# Schematic.net
KiCad netlist of a schematic drawn in Altium Designer
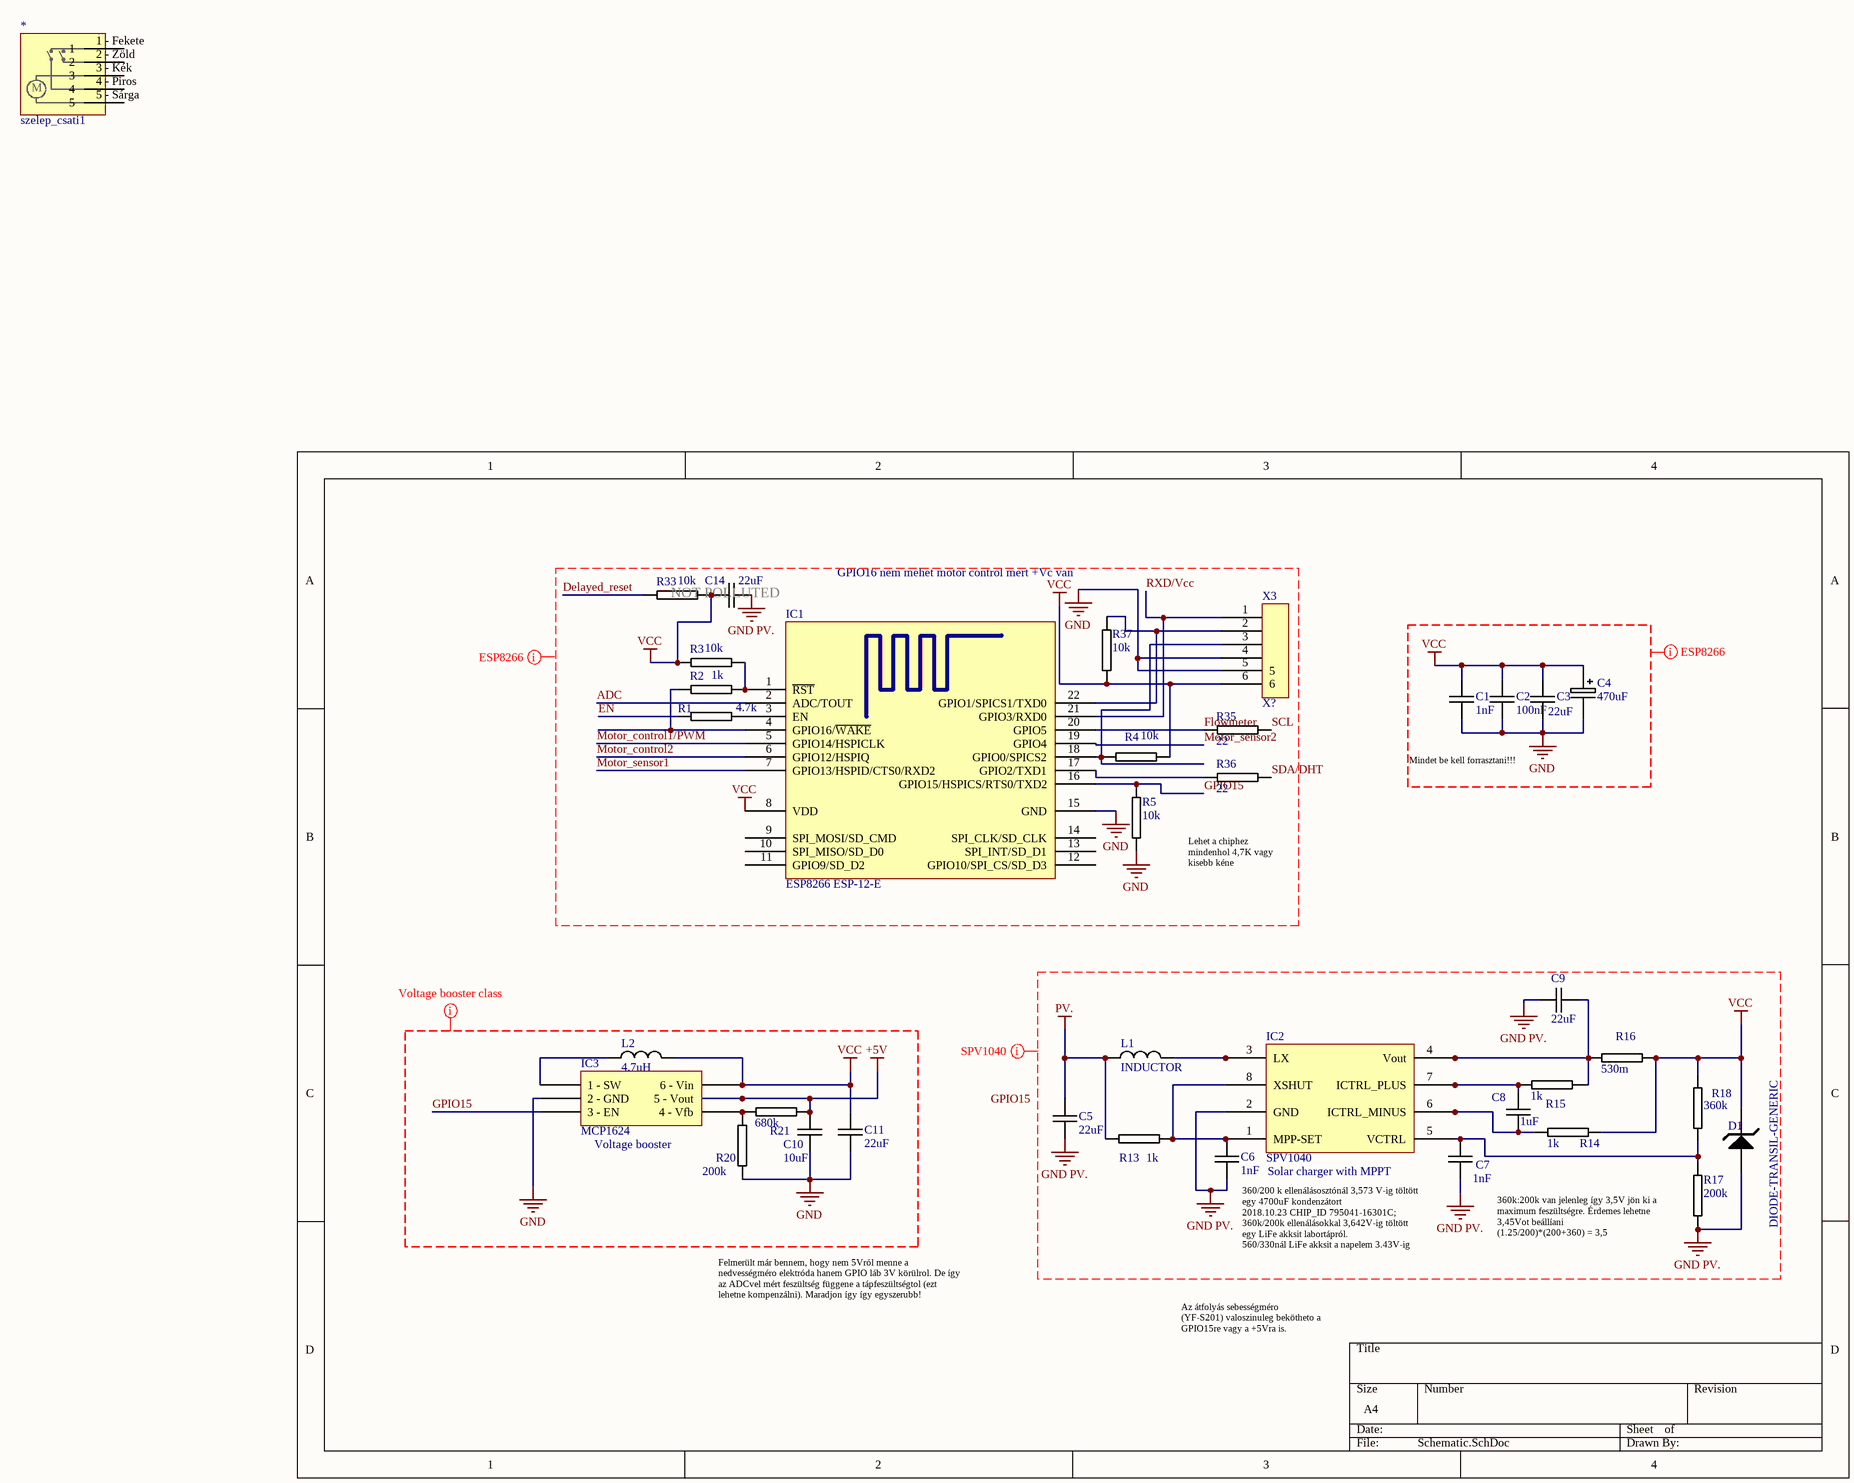
[diagram p0: Schematic.SchDoc]

(export (version "E")
  (design (tool "Eeschema 10.0.6"))
  (components
    (comp (ref "*")
      (value "szelep_csati1")
      (footprint "Szelep_csati")
      (libsource (lib "components") (part "szelep_csati1"))
    )
    (comp (ref "C1")
      (value "1nF")
      (footprint "0805C-TBD")
      (description "CAPACITOR 0805 CERAMIC")
      (libsource (lib "vh_altium_library") (part "0805C-100nF-25V-X7R-MUR"))
    )
    (comp (ref "C2")
      (value "100nF")
      (footprint "1206C-GENERIC")
      (description "GENERIC CAPACITOR NON POLARISED 1206")
      (fields
        (field (name "MANUFACTURER PART NUMBER") "GMK316F106ZL-T")
        (field (name "MANUFACTURER") "Taiyo Yuden")
      )
      (libsource (lib "vh_altium_library") (part "1206C-10U-35V-X7R"))
    )
    (comp (ref "C3")
      (value "22uF")
      (footprint "1206C-GENERIC")
      (description "GENERIC CAPACITOR NON POLARISED 1206")
      (fields
        (field (name "MANUFACTURER PART NUMBER") "GMK316F106ZL-T")
        (field (name "MANUFACTURER") "Taiyo Yuden")
      )
      (libsource (lib "vh_altium_library") (part "1206C-10U-35V-X7R"))
    )
    (comp (ref "C4")
      (value "470uF")
      (footprint "PANACAP-D-GENERIC")
      (description "GENERIC CAPACITOR POLARISED")
      (libsource (lib "vh_altium_library") (part "C+47U-6V3"))
    )
    (comp (ref "C5")
      (value "22uF")
      (footprint "1206C-GENERIC")
      (description "GENERIC CAPACITOR NON POLARISED 1206")
      (fields
        (field (name "MANUFACTURER PART NUMBER") "GMK316F106ZL-T")
        (field (name "MANUFACTURER") "Taiyo Yuden")
      )
      (libsource (lib "vh_altium_library") (part "1206C-10U-35V-X7R"))
    )
    (comp (ref "C6")
      (value "1nF")
      (footprint "CAPC200X125X100L40N")
      (description "CAPACITOR 0805 CERAMIC")
      (libsource (lib "vh_altium_library") (part "0805C-100nF-25V-X7R-MUR"))
    )
    (comp (ref "C7")
      (value "1nF")
      (footprint "CAPC200X125X100L40N")
      (description "CAPACITOR 0805 CERAMIC")
      (libsource (lib "components") (part "0805C-100nF-25V-X7R-MUR"))
    )
    (comp (ref "C8")
      (value "1uF")
      (footprint "CAPC200X125X100L40N")
      (description "CAPACITOR 0805 CERAMIC VALUE TO BE DETERMINED")
      (libsource (lib "SMD Capacitors 0805") (part "0805C-TBD"))
    )
    (comp (ref "C9")
      (value "22uF")
      (footprint "CAPC320X160X50L40N")
      (description "GENERIC CAPACITOR NON POLARISED 1206")
      (fields
        (field (name "MANUFACTURER PART NUMBER") "GMK316F106ZL-T")
        (field (name "MANUFACTURER") "Taiyo Yuden")
      )
      (libsource (lib "vh_altium_library") (part "1206C-10U-35V-X7R"))
    )
    (comp (ref "C10")
      (value "10uF")
      (footprint "1206C-GENERIC")
      (description "GENERIC CAPACITOR NON POLARISED 1206")
      (fields
        (field (name "MANUFACTURER PART NUMBER") "GMK316F106ZL-T")
        (field (name "MANUFACTURER") "Taiyo Yuden")
      )
      (libsource (lib "vh_altium_library") (part "1206C-10U-35V-X7R"))
    )
    (comp (ref "C11")
      (value "22uF")
      (footprint "1206C-GENERIC")
      (description "GENERIC CAPACITOR NON POLARISED 1206")
      (fields
        (field (name "MANUFACTURER PART NUMBER") "GMK316F106ZL-T")
        (field (name "MANUFACTURER") "Taiyo Yuden")
      )
      (libsource (lib "vh_altium_library") (part "1206C-10U-35V-X7R"))
    )
    (comp (ref "C14")
      (value "22uF")
      (footprint "0805C-GENERIC")
      (description "GENERIC CAPACITOR NON POLARISED0603")
      (libsource (lib "vh_altium_library") (part "C0805-GENERIC"))
    )
    (comp (ref "D1")
      (value "DIODE-TRANSIL-GENERIC")
      (footprint "SOD523")
      (description "GENERIC TRANSIL")
      (libsource (lib "vh_altium_library") (part "DIODE-TRANSIL-GENERIC"))
    )
    (comp (ref "IC1")
      (value "ESP8266 ESP-12-E")
      (footprint "ESP8266:ESP8266 ESP-12-E")
      (libsource (lib "ESP8266") (part "ESP8266 ESP-12-E"))
    )
    (comp (ref "IC2") (value "SPV1040") (footprint "SPV1040") (libsource (lib "components") (part "SPV1040")))
    (comp (ref "IC3") (value "MCP1624") (footprint "SOT23-6") (libsource (lib "MCP1623") (part "MCP1623")))
    (comp (ref "L1")
      (value "INDUCTOR")
      (footprint "INDM730X660X300L160X290N")
      (fields (field (name "LCSC PART #") "C132141"))
      (libsource (lib "vh_altium_library") (part "INDUCTOR"))
    )
    (comp (ref "L2")
      (value "4.7uH")
      (footprint "INDM2520X190N")
      (description "INDUCTOR")
      (fields (field (name "LCSC PART #") "C1049"))
      (libsource (lib "vh_altium_library") (part "INDUCTOR"))
    )
    (comp (ref "R1")
      (value "4.7k")
      (footprint "0805R-10K")
      (description "RESISTOR 0805 1/4 WATT THIN FILM")
      (libsource (lib "vh_altium_library") (part "0805R-10K"))
    )
    (comp (ref "R2")
      (value "1k")
      (footprint "1206FB-50Z")
      (description "0 vagy talan 1K? RESISTOR 0805 1/3 WATT")
      (libsource (lib "vh_altium_library") (part "0805R-1R"))
    )
    (comp (ref "R3")
      (value "10k")
      (footprint "0805R-10K")
      (description "RESISTOR 0805 1/4 WATT THIN FILM")
      (libsource (lib "vh_altium_library") (part "0805R-10K"))
    )
    (comp (ref "R4")
      (value "10k")
      (footprint "1206C-GENERIC")
      (description "RESISTOR 0805 1/4 WATT THIN FILM")
      (libsource (lib "vh_altium_library") (part "0805R-10K"))
    )
    (comp (ref "R5")
      (value "10k")
      (footprint "0805R-10K")
      (description "RESISTOR 0805 1/4 WATT THIN FILM")
      (libsource (lib "vh_altium_library") (part "0805R-10K"))
    )
    (comp (ref "R13")
      (value "1k")
      (footprint "RESC200X125X70L40N")
      (description "RESISTOR 0805 1/3 WATT")
      (libsource (lib "vh_altium_library") (part "0805R-1R"))
    )
    (comp (ref "R14")
      (value "1k")
      (footprint "RESC200X125X70L40N")
      (description "RESISTOR 0805 1/4 WATT THIN FILM")
      (libsource (lib "vh_altium_library") (part "0805R-1K"))
    )
    (comp (ref "R15")
      (value "1k")
      (footprint "RESC200X125X70L40N")
      (description "RESISTOR 0805 1/4 WATT THIN FILM")
      (libsource (lib "vh_altium_library") (part "0805R-1K"))
    )
    (comp (ref "R16")
      (value "530m")
      (footprint "RESC200X125X70L40N")
      (description "RESISTOR 0805 1/3 WATT")
      (libsource (lib "vh_altium_library") (part "0805R-1R"))
    )
    (comp (ref "R17")
      (value "200k")
      (footprint "RESC200X125X70L40N")
      (description "RESISTOR 0805 1/4 WATT THIN FILM")
      (libsource (lib "vh_altium_library") (part "0805R-680K"))
    )
    (comp (ref "R18")
      (value "360k")
      (footprint "RESC200X125X70L40N")
      (description "RESISTOR 0805 1/4 WATT THIN FILM")
      (libsource (lib "vh_altium_library") (part "0805R-680K"))
    )
    (comp (ref "R20")
      (value "200k")
      (footprint "RESC200X125X70L40N")
      (description "RESISTOR 0805 1/4 WATT THIN FILM")
      (libsource (lib "vh_altium_library") (part "0805R-820K"))
    )
    (comp (ref "R21")
      (value "680k")
      (footprint "RESC200X125X70L40N")
      (description "RESISTOR 0805 1/4 WATT THIN FILM")
      (libsource (lib "vh_altium_library") (part "0805R-560K"))
    )
    (comp (ref "R33")
      (value "10k")
      (footprint "0805R-10K")
      (description "RESISTOR 0805 1/4 WATT THIN FILM")
      (libsource (lib "vh_altium_library") (part "0805R-10K"))
    )
    (comp (ref "R35")
      (value "22")
      (footprint "0805R-22")
      (description "RESISTOR 0805 1/4 WATT THIN FILM")
      (libsource (lib "vh_altium_library") (part "0805R-22"))
    )
    (comp (ref "R36")
      (value "22")
      (footprint "0805R-22")
      (description "RESISTOR 0805 1/4 WATT THIN FILM")
      (libsource (lib "vh_altium_library") (part "0805R-22"))
    )
    (comp (ref "R37")
      (value "10k")
      (footprint "0805R-22")
      (description "RESISTOR 0805 1/4 WATT THIN FILM")
      (libsource (lib "vh_altium_library") (part "0805R-22"))
    )
    (comp (ref "X3")
      (value "X?")
      (footprint "program port")
      (libsource (lib "components") (part "program port"))
    )
  )
  (nets
    (net (code "1") (name "+5V") (class "Default")
      (node (ref "C10") (pin "1") (pintype "passive"))
      (node (ref "IC3") (pin "5") (pinfunction "5_-_Vout_5") (pintype "passive"))
      (node (ref "R21") (pin "2") (pintype "passive"))
    )
    (net (code "2") (name "/ADC") (class "Default")
      (node (ref "IC1") (pin "2") (pinfunction "ADC/TOUT_2") (pintype "passive"))
    )
    (net (code "3") (name "/Delayed_reset") (class "Default")
      (node (ref "R33") (pin "1") (pintype "passive"))
    )
    (net (code "4") (name "/EN") (class "Default") (node (ref "R1") (pin "1") (pintype "passive")))
    (net (code "5") (name "/Flowmeter") (class "Default")
      (node (ref "IC1") (pin "20") (pinfunction "GPIO5_20") (pintype "passive"))
      (node (ref "R35") (pin "2") (pintype "passive"))
    )
    (net (code "6") (name "/GPIO15") (class "Default")
      (node (ref "IC1") (pin "16") (pinfunction "GPIO15/HSPICS/RTS0/TXD2_16") (pintype "passive"))
      (node (ref "IC3") (pin "3") (pinfunction "3_-_EN_3") (pintype "passive"))
      (node (ref "R5") (pin "2") (pintype "passive"))
    )
    (net (code "7") (name "/Motor_control1{slash}PWM") (class "Default")
      (node (ref "IC1") (pin "5") (pinfunction "GPIO14/HSPICLK_5") (pintype "passive"))
    )
    (net (code "8") (name "/Motor_control2") (class "Default")
      (node (ref "IC1") (pin "6") (pinfunction "GPIO12/HSPIQ_6") (pintype "passive"))
    )
    (net (code "9") (name "/Motor_sensor1") (class "Default")
      (node (ref "IC1") (pin "7") (pinfunction "GPIO13/HSPID/CTS0/RXD2_7") (pintype "passive"))
    )
    (net (code "10") (name "/Motor_sensor2") (class "Default")
      (node (ref "IC1") (pin "19") (pinfunction "GPIO4_19") (pintype "passive"))
    )
    (net (code "11") (name "/RXD{slash}Vcc") (class "Default")
      (node (ref "IC1") (pin "21") (pinfunction "GPIO3/RXD0_21") (pintype "passive"))
      (node (ref "X3") (pin "1") (pinfunction "1_1") (pintype "passive"))
    )
    (net (code "12") (name "/SCL") (class "Default") (node (ref "R35") (pin "1") (pintype "passive")))
    (net (code "13") (name "/SDA{slash}DHT") (class "Default")
      (node (ref "R36") (pin "1") (pintype "passive"))
    )
    (net (code "14") (name "GND") (class "Default")
      (node (ref "C1") (pin "2") (pintype "passive"))
      (node (ref "C10") (pin "2") (pintype "passive"))
      (node (ref "C11") (pin "2") (pintype "passive"))
      (node (ref "C2") (pin "2") (pintype "passive"))
      (node (ref "C3") (pin "2") (pintype "passive"))
      (node (ref "C4") (pin "-") (pinfunction "-_-") (pintype "passive"))
      (node (ref "IC1") (pin "15") (pinfunction "GND_15") (pintype "passive"))
      (node (ref "IC3") (pin "2") (pinfunction "2_-_GND_2") (pintype "passive"))
      (node (ref "R20") (pin "2") (pintype "passive"))
      (node (ref "R5") (pin "1") (pintype "passive"))
      (node (ref "X3") (pin "4") (pinfunction "4_4") (pintype "passive"))
      (node (ref "X3") (pin "5") (pinfunction "5_5") (pintype "passive"))
    )
    (net (code "15") (name "GND PV.") (class "Default")
      (node (ref "C14") (pin "2") (pintype "passive"))
      (node (ref "C5") (pin "2") (pintype "passive"))
      (node (ref "C6") (pin "2") (pintype "passive"))
      (node (ref "C7") (pin "2") (pintype "passive"))
      (node (ref "C9") (pin "1") (pintype "passive"))
      (node (ref "D1") (pin "A") (pinfunction "A_A") (pintype "passive"))
      (node (ref "IC2") (pin "2") (pinfunction "GND_2") (pintype "passive"))
      (node (ref "R17") (pin "2") (pintype "passive"))
    )
    (net (code "16") (name "Net-(IC1-EN)") (class "Default")
      (node (ref "IC1") (pin "3") (pinfunction "EN_3") (pintype "passive"))
      (node (ref "R1") (pin "2") (pintype "passive"))
    )
    (net (code "17") (name "Net-(IC1-GPIO0{slash}SPICS2)") (class "Default")
      (node (ref "IC1") (pin "18") (pinfunction "GPIO0/SPICS2_18") (pintype "passive"))
      (node (ref "R4") (pin "1") (pintype "passive"))
      (node (ref "X3") (pin "3") (pinfunction "2_3") (pintype "passive"))
    )
    (net (code "18") (name "Net-(IC1-GPIO1{slash}SPICS1{slash}TXD0)") (class "Default")
      (node (ref "IC1") (pin "22") (pinfunction "GPIO1/SPICS1/TXD0_22") (pintype "passive"))
      (node (ref "R37") (pin "1") (pintype "passive"))
      (node (ref "X3") (pin "2") (pinfunction "2_2") (pintype "passive"))
    )
    (net (code "19") (name "Net-(IC1-GPIO2{slash}TXD1)") (class "Default")
      (node (ref "IC1") (pin "17") (pinfunction "GPIO2/TXD1_17") (pintype "passive"))
      (node (ref "R36") (pin "2") (pintype "passive"))
    )
    (net (code "20") (name "Net-(IC1-GPIO16{slash}~{WAKE})") (class "Default")
      (node (ref "IC1") (pin "4") (pinfunction "GPIO16/~{WAKE}_4") (pintype "passive"))
      (node (ref "R2") (pin "2") (pintype "passive"))
    )
    (net (code "21") (name "Net-(IC1-~{RST})") (class "Default")
      (node (ref "IC1") (pin "1") (pinfunction "~{RST}_1") (pintype "passive"))
      (node (ref "R2") (pin "1") (pintype "passive"))
      (node (ref "R3") (pin "2") (pintype "passive"))
    )
    (net (code "22") (name "Net-(IC2-ICTRL_MINUS)") (class "Default")
      (node (ref "C8") (pin "2") (pintype "passive"))
      (node (ref "IC2") (pin "6") (pinfunction "ICTRL_MINUS_6") (pintype "passive"))
      (node (ref "R14") (pin "2") (pintype "passive"))
    )
    (net (code "23") (name "Net-(IC2-ICTRL_PLUS)") (class "Default")
      (node (ref "C8") (pin "1") (pintype "passive"))
      (node (ref "IC2") (pin "7") (pinfunction "ICTRL_PLUS_7") (pintype "passive"))
      (node (ref "R15") (pin "2") (pintype "passive"))
    )
    (net (code "24") (name "Net-(IC2-LX)") (class "Default")
      (node (ref "IC2") (pin "3") (pinfunction "LX_3") (pintype "passive"))
      (node (ref "L1") (pin "2") (pinfunction "2_2") (pintype "passive"))
    )
    (net (code "25") (name "Net-(IC2-MPP-SET)") (class "Default")
      (node (ref "C6") (pin "1") (pintype "passive"))
      (node (ref "IC2") (pin "1") (pinfunction "MPP-SET_1") (pintype "passive"))
      (node (ref "IC2") (pin "8") (pinfunction "XSHUT_8") (pintype "passive"))
      (node (ref "R13") (pin "1") (pintype "passive"))
    )
    (net (code "26") (name "Net-(IC2-VCTRL)") (class "Default")
      (node (ref "C7") (pin "1") (pintype "passive"))
      (node (ref "IC2") (pin "5") (pinfunction "VCTRL_5") (pintype "passive"))
      (node (ref "R17") (pin "1") (pintype "passive"))
      (node (ref "R18") (pin "2") (pintype "passive"))
    )
    (net (code "27") (name "Net-(IC2-Vout)") (class "Default")
      (node (ref "C9") (pin "2") (pintype "passive"))
      (node (ref "IC2") (pin "4") (pinfunction "Vout_4") (pintype "passive"))
      (node (ref "R15") (pin "1") (pintype "passive"))
      (node (ref "R16") (pin "2") (pintype "passive"))
    )
    (net (code "28") (name "Net-(IC3-1_-_SW)") (class "Default")
      (node (ref "IC3") (pin "1") (pinfunction "1_-_SW_1") (pintype "passive"))
      (node (ref "L2") (pin "1") (pinfunction "1_1") (pintype "passive"))
    )
    (net (code "29") (name "Net-(IC3-4_-_Vfb)") (class "Default")
      (node (ref "IC3") (pin "4") (pinfunction "4_-_Vfb_4") (pintype "passive"))
      (node (ref "R20") (pin "1") (pintype "passive"))
      (node (ref "R21") (pin "1") (pintype "passive"))
    )
    (net (code "30") (name "PV.") (class "Default")
      (node (ref "C5") (pin "1") (pintype "passive"))
      (node (ref "L1") (pin "1") (pinfunction "1_1") (pintype "passive"))
      (node (ref "R13") (pin "2") (pintype "passive"))
    )
    (net (code "31") (name "VCC") (class "Default")
      (node (ref "C1") (pin "1") (pintype "passive"))
      (node (ref "C11") (pin "1") (pintype "passive"))
      (node (ref "C14") (pin "1") (pintype "passive"))
      (node (ref "C2") (pin "1") (pintype "passive"))
      (node (ref "C3") (pin "1") (pintype "passive"))
      (node (ref "C4") (pin "+") (pinfunction "+_+") (pintype "passive"))
      (node (ref "D1") (pin "K") (pinfunction "K_K") (pintype "passive"))
      (node (ref "IC1") (pin "8") (pinfunction "VDD_8") (pintype "passive"))
      (node (ref "IC3") (pin "6") (pinfunction "6_-_Vin_6") (pintype "passive"))
      (node (ref "L2") (pin "2") (pinfunction "2_2") (pintype "passive"))
      (node (ref "R14") (pin "1") (pintype "passive"))
      (node (ref "R16") (pin "1") (pintype "passive"))
      (node (ref "R18") (pin "1") (pintype "passive"))
      (node (ref "R3") (pin "1") (pintype "passive"))
      (node (ref "R33") (pin "2") (pintype "passive"))
      (node (ref "R37") (pin "2") (pintype "passive"))
      (node (ref "R4") (pin "2") (pintype "passive"))
      (node (ref "X3") (pin "6") (pinfunction "6_6") (pintype "passive"))
    )
    (net (code "32") (name "unconnected-(*-1-Pad1_-_Fekete)") (class "Default")
      (node (ref "*") (pin "1_-_Fekete") (pinfunction "1_1_-_Fekete") (pintype "passive"))
    )
    (net (code "33") (name "unconnected-(*-2-Pad2_-_Zöld)") (class "Default")
      (node (ref "*") (pin "2_-_Zöld") (pinfunction "2_2_-_Zöld") (pintype "passive"))
    )
    (net (code "34") (name "unconnected-(*-3-Pad3_-_Kék)") (class "Default")
      (node (ref "*") (pin "3_-_Kék") (pinfunction "3_3_-_Kék") (pintype "passive"))
    )
    (net (code "35") (name "unconnected-(*-4-Pad4_-_Piros)") (class "Default")
      (node (ref "*") (pin "4_-_Piros") (pinfunction "4_4_-_Piros") (pintype "passive"))
    )
    (net (code "36") (name "unconnected-(*-5-Pad5_-_Sárga)") (class "Default")
      (node (ref "*") (pin "5_-_Sárga") (pinfunction "5_5_-_Sárga") (pintype "passive"))
    )
    (net (code "37") (name "unconnected-(IC1-GPIO9{slash}SD_D2-Pad11)") (class "Default")
      (node (ref "IC1") (pin "11") (pinfunction "GPIO9/SD_D2_11") (pintype "passive"))
    )
    (net (code "38") (name "unconnected-(IC1-GPIO10{slash}SPI_CS{slash}SD_D3-Pad12)") (class "Default")
      (node (ref "IC1") (pin "12") (pinfunction "GPIO10/SPI_CS/SD_D3_12") (pintype "passive"))
    )
    (net (code "39") (name "unconnected-(IC1-SPI_CLK{slash}SD_CLK-Pad14)") (class "Default")
      (node (ref "IC1") (pin "14") (pinfunction "SPI_CLK/SD_CLK_14") (pintype "passive"))
    )
    (net (code "40") (name "unconnected-(IC1-SPI_INT{slash}SD_D1-Pad13)") (class "Default")
      (node (ref "IC1") (pin "13") (pinfunction "SPI_INT/SD_D1_13") (pintype "passive"))
    )
    (net (code "41") (name "unconnected-(IC1-SPI_MISO{slash}SD_D0-Pad10)") (class "Default")
      (node (ref "IC1") (pin "10") (pinfunction "SPI_MISO/SD_D0_10") (pintype "passive"))
    )
    (net (code "42") (name "unconnected-(IC1-SPI_MOSI{slash}SD_CMD-Pad9)") (class "Default")
      (node (ref "IC1") (pin "9") (pinfunction "SPI_MOSI/SD_CMD_9") (pintype "passive"))
    )
  )
)
